# mfrhp.net
KiCad netlist of a schematic drawn in EAGLE
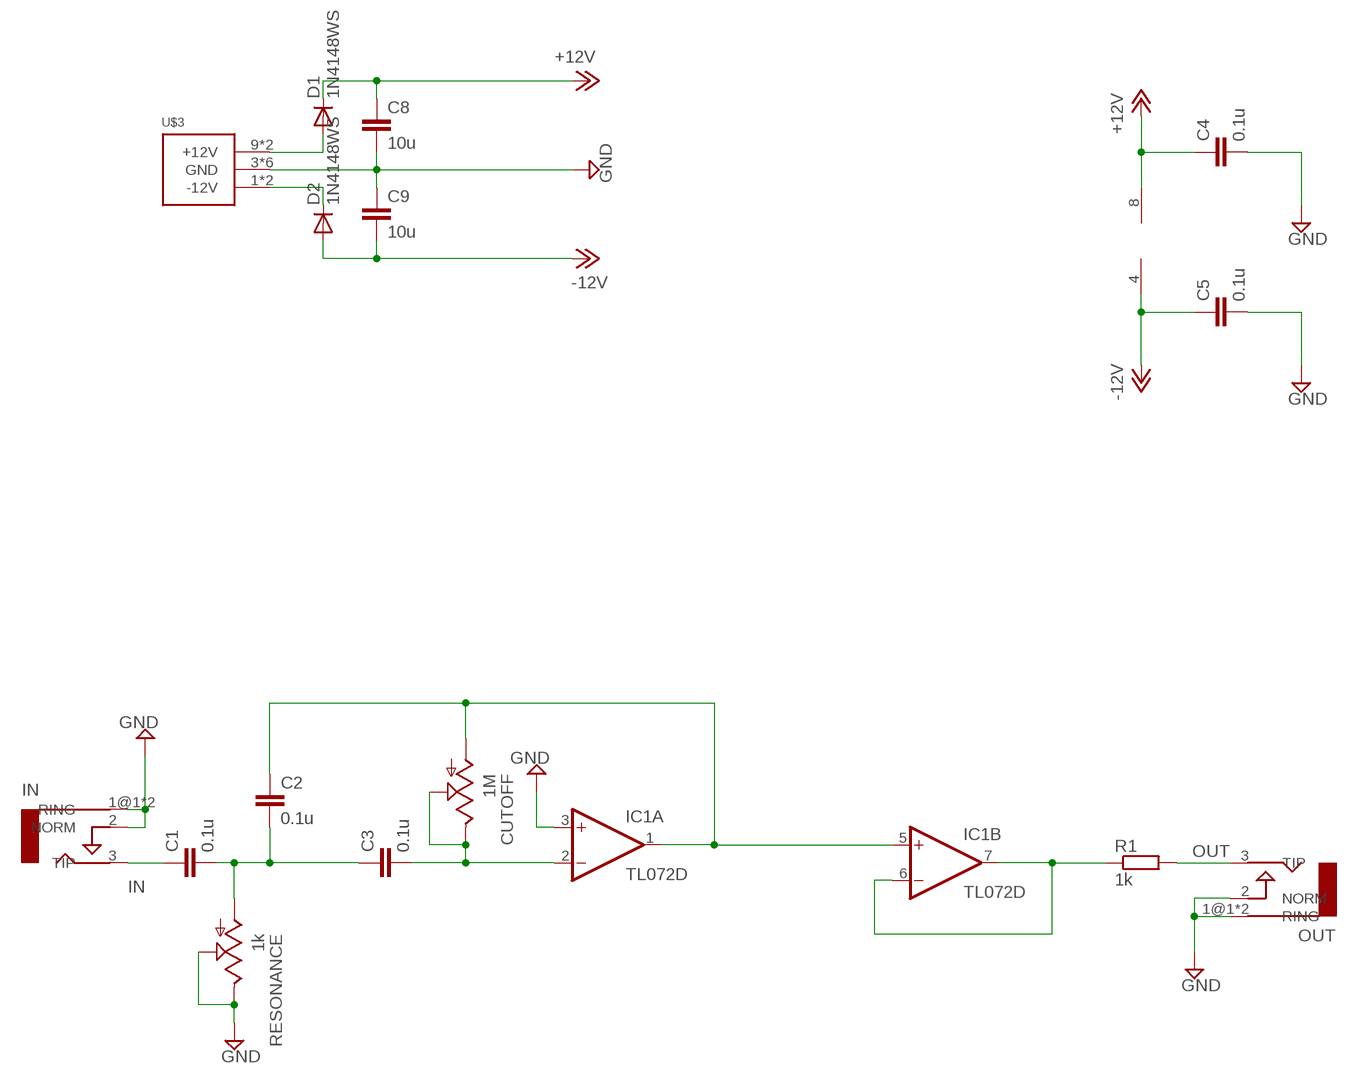
[diagram p0: schematic, sheet 1]

(export (version "E")
  (design (tool "Eeschema 10.0.6"))
  (components
    (comp (ref "C1")
      (value "0.1u")
      (footprint "eagle-import:C0805")
      (libsource (lib "eagle-import") (part "C-EUC0805"))
    )
    (comp (ref "C2")
      (value "0.1u")
      (footprint "eagle-import:C0805")
      (libsource (lib "eagle-import") (part "C-EUC0805"))
    )
    (comp (ref "C3")
      (value "0.1u")
      (footprint "eagle-import:C0805")
      (libsource (lib "eagle-import") (part "C-EUC0805"))
    )
    (comp (ref "C4")
      (value "0.1u")
      (footprint "eagle-import:C0805")
      (libsource (lib "eagle-import") (part "C-EUC0805"))
    )
    (comp (ref "C5")
      (value "0.1u")
      (footprint "eagle-import:C0805")
      (libsource (lib "eagle-import") (part "C-EUC0805"))
    )
    (comp (ref "C8")
      (value "10u")
      (footprint "eagle-import:C0805")
      (libsource (lib "eagle-import") (part "C-EUC0805"))
    )
    (comp (ref "C9")
      (value "10u")
      (footprint "eagle-import:C0805")
      (libsource (lib "eagle-import") (part "C-EUC0805"))
    )
    (comp (ref "CUTOFF")
      (value "1M")
      (footprint "eagle-import:9MM_SNAP-IN_POT")
      (libsource (lib "eagle-import") (part "9MM_SNAP-IN_POT_"))
    )
    (comp (ref "D1")
      (value "1N4148WS")
      (footprint "eagle-import:SOD323-W")
      (libsource (lib "eagle-import") (part "DIODE-SOD323-W"))
    )
    (comp (ref "D2")
      (value "1N4148WS")
      (footprint "eagle-import:SOD323-W")
      (libsource (lib "eagle-import") (part "DIODE-SOD323-W"))
    )
    (comp (ref "IC1")
      (value "TL072D")
      (footprint "eagle-import:SO08")
      (libsource (lib "eagle-import") (part "TL072D"))
    )
    (comp (ref "IN")
      (value "AUDIO-JACKERTHENVAR")
      (footprint "eagle-import:ERTHENVAR-JACK")
      (libsource (lib "eagle-import") (part "AUDIO-JACKERTHENVAR"))
    )
    (comp (ref "OUT")
      (value "AUDIO-JACKERTHENVAR")
      (footprint "eagle-import:ERTHENVAR-JACK")
      (libsource (lib "eagle-import") (part "AUDIO-JACKERTHENVAR"))
    )
    (comp (ref "R1")
      (value "1k")
      (footprint "eagle-import:R0805")
      (libsource (lib "eagle-import") (part "R-EU_R0805"))
    )
    (comp (ref "RESONANCE")
      (value "1k")
      (footprint "eagle-import:9MM_SNAP-IN_POT")
      (libsource (lib "eagle-import") (part "9MM_SNAP-IN_POT_"))
    )
    (comp (ref "U$3")
      (value "POWER_SIMPLE10")
      (footprint "eagle-import:POWER_10")
      (libsource (lib "eagle-import") (part "POWER_SIMPLE10"))
    )
  )
  (nets
    (net (code "1") (name "+12V") (class "Default")
      (node (ref "C4") (pin "1") (pinfunction "1_1") (pintype "passive"))
      (node (ref "C8") (pin "1") (pinfunction "1_1") (pintype "passive"))
      (node (ref "D1") (pin "C") (pinfunction "C_C") (pintype "passive"))
      (node (ref "IC1") (pin "8") (pinfunction "V+_8") (pintype "power_in"))
    )
    (net (code "2") (name "-12V") (class "Default")
      (node (ref "C5") (pin "1") (pinfunction "1_1") (pintype "passive"))
      (node (ref "C9") (pin "2") (pinfunction "2_2") (pintype "passive"))
      (node (ref "D2") (pin "A") (pinfunction "A_A") (pintype "passive"))
      (node (ref "IC1") (pin "4") (pinfunction "V-_4") (pintype "power_in"))
    )
    (net (code "3") (name "/IN") (class "Default")
      (node (ref "C1") (pin "1") (pinfunction "1_1") (pintype "passive"))
      (node (ref "IN") (pin "3") (pinfunction "TIP_3") (pintype "bidirectional"))
    )
    (net (code "4") (name "/OUT") (class "Default")
      (node (ref "OUT") (pin "3") (pinfunction "TIP_3") (pintype "bidirectional"))
      (node (ref "R1") (pin "2") (pinfunction "2_2") (pintype "passive"))
    )
    (net (code "5") (name "GND") (class "Default")
      (node (ref "C4") (pin "2") (pinfunction "2_2") (pintype "passive"))
      (node (ref "C5") (pin "2") (pinfunction "2_2") (pintype "passive"))
      (node (ref "C8") (pin "2") (pinfunction "2_2") (pintype "passive"))
      (node (ref "C9") (pin "1") (pinfunction "1_1") (pintype "passive"))
      (node (ref "IC1") (pin "3") (pinfunction "+IN_3") (pintype "input"))
      (node (ref "IN") (pin "1@1") (pinfunction "RING_1@1") (pintype "bidirectional"))
      (node (ref "IN") (pin "1@2") (pinfunction "RING_1@2") (pintype "bidirectional"))
      (node (ref "IN") (pin "2") (pinfunction "NORM_2") (pintype "bidirectional"))
      (node (ref "OUT") (pin "1@1") (pinfunction "RING_1@1") (pintype "bidirectional"))
      (node (ref "OUT") (pin "1@2") (pinfunction "RING_1@2") (pintype "bidirectional"))
      (node (ref "OUT") (pin "2") (pinfunction "NORM_2") (pintype "bidirectional"))
      (node (ref "RESONANCE") (pin "2") (pinfunction "S_2") (pintype "passive"))
      (node (ref "RESONANCE") (pin "3") (pinfunction "E_3") (pintype "passive"))
      (node (ref "U$3") (pin "3") (pinfunction "GND_3") (pintype "bidirectional"))
      (node (ref "U$3") (pin "4") (pinfunction "GND_4") (pintype "bidirectional"))
      (node (ref "U$3") (pin "5") (pinfunction "GND_5") (pintype "bidirectional"))
      (node (ref "U$3") (pin "6") (pinfunction "GND_6") (pintype "bidirectional"))
      (node (ref "U$3") (pin "7") (pinfunction "GND_7") (pintype "bidirectional"))
      (node (ref "U$3") (pin "8") (pinfunction "GND_8") (pintype "bidirectional"))
    )
    (net (code "6") (name "Net-(CUTOFF-A)") (class "Default")
      (node (ref "C2") (pin "1") (pinfunction "1_1") (pintype "passive"))
      (node (ref "CUTOFF") (pin "1") (pinfunction "A_1") (pintype "passive"))
      (node (ref "IC1") (pin "1") (pinfunction "OUT_1") (pintype "output"))
      (node (ref "IC1") (pin "5") (pinfunction "+IN_5") (pintype "input"))
    )
    (net (code "7") (name "Net-(CUTOFF-E)") (class "Default")
      (node (ref "C3") (pin "2") (pinfunction "2_2") (pintype "passive"))
      (node (ref "CUTOFF") (pin "2") (pinfunction "S_2") (pintype "passive"))
      (node (ref "CUTOFF") (pin "3") (pinfunction "E_3") (pintype "passive"))
      (node (ref "IC1") (pin "2") (pinfunction "-IN_2") (pintype "input"))
    )
    (net (code "8") (name "Net-(D1-PadA)") (class "Default")
      (node (ref "D1") (pin "A") (pinfunction "A_A") (pintype "passive"))
      (node (ref "U$3") (pin "10") (pinfunction "+12V_10") (pintype "bidirectional"))
      (node (ref "U$3") (pin "9") (pinfunction "+12V_9") (pintype "bidirectional"))
    )
    (net (code "9") (name "Net-(D2-PadC)") (class "Default")
      (node (ref "D2") (pin "C") (pinfunction "C_C") (pintype "passive"))
      (node (ref "U$3") (pin "1") (pinfunction "-12V_1") (pintype "bidirectional"))
      (node (ref "U$3") (pin "2") (pinfunction "-12V_2") (pintype "bidirectional"))
    )
    (net (code "10") (name "Net-(IC1B--IN)") (class "Default")
      (node (ref "IC1") (pin "6") (pinfunction "-IN_6") (pintype "input"))
      (node (ref "IC1") (pin "7") (pinfunction "OUT_7") (pintype "output"))
      (node (ref "R1") (pin "1") (pinfunction "1_1") (pintype "passive"))
    )
    (net (code "11") (name "Net-(RESONANCE-A)") (class "Default")
      (node (ref "C1") (pin "2") (pinfunction "2_2") (pintype "passive"))
      (node (ref "C2") (pin "2") (pinfunction "2_2") (pintype "passive"))
      (node (ref "C3") (pin "1") (pinfunction "1_1") (pintype "passive"))
      (node (ref "RESONANCE") (pin "1") (pinfunction "A_1") (pintype "passive"))
    )
  )
)
